# Turnout_Decoder_V1_1.net
KiCad netlist of a schematic drawn in EAGLE
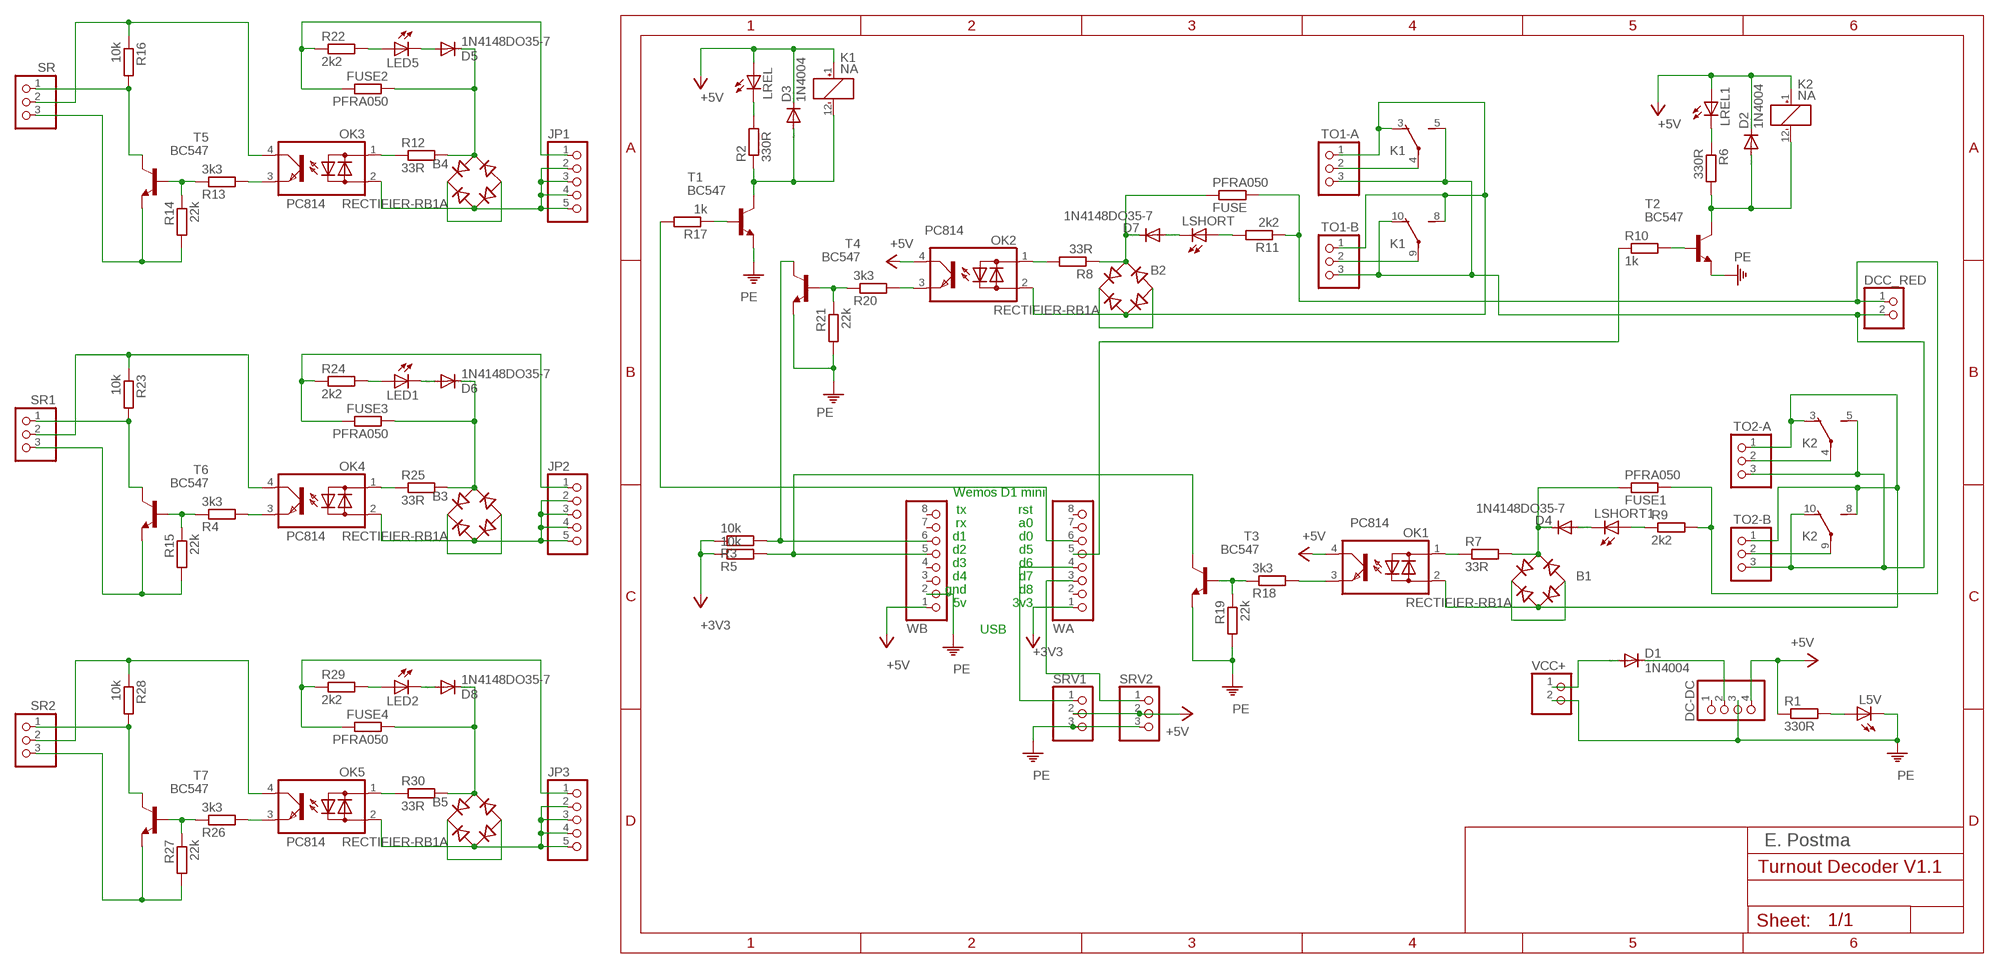
[diagram p0: schematic, sheet 1]

(export (version "E")
  (design (tool "Eeschema 10.0.6"))
  (components
    (comp (ref "B1")
      (value "RECTIFIER-RB1A")
      (footprint "eagle-import:RB1A")
      (libsource (lib "eagle-import") (part "RECTIFIER-RB1A"))
    )
    (comp (ref "B2")
      (value "RECTIFIER-RB1A")
      (footprint "eagle-import:RB1A")
      (libsource (lib "eagle-import") (part "RECTIFIER-RB1A"))
    )
    (comp (ref "B3")
      (value "RECTIFIER-RB1A")
      (footprint "eagle-import:RB1A")
      (libsource (lib "eagle-import") (part "RECTIFIER-RB1A"))
    )
    (comp (ref "B4")
      (value "RECTIFIER-RB1A")
      (footprint "eagle-import:RB1A")
      (libsource (lib "eagle-import") (part "RECTIFIER-RB1A"))
    )
    (comp (ref "B5")
      (value "RECTIFIER-RB1A")
      (footprint "eagle-import:RB1A")
      (libsource (lib "eagle-import") (part "RECTIFIER-RB1A"))
    )
    (comp (ref "D1")
      (value "1N4004")
      (footprint "eagle-import:DO41-10")
      (libsource (lib "eagle-import") (part "1N4004"))
    )
    (comp (ref "D2")
      (value "1N4004")
      (footprint "eagle-import:DO41-10")
      (libsource (lib "eagle-import") (part "1N4004"))
    )
    (comp (ref "D3")
      (value "1N4004")
      (footprint "eagle-import:DO41-10")
      (libsource (lib "eagle-import") (part "1N4004"))
    )
    (comp (ref "D4")
      (value "1N4148DO35-7")
      (footprint "eagle-import:DO35-7")
      (libsource (lib "eagle-import") (part "1N4148DO35-7"))
    )
    (comp (ref "D5")
      (value "1N4148DO35-7")
      (footprint "eagle-import:DO35-7")
      (libsource (lib "eagle-import") (part "1N4148DO35-7"))
    )
    (comp (ref "D6")
      (value "1N4148DO35-7")
      (footprint "eagle-import:DO35-7")
      (libsource (lib "eagle-import") (part "1N4148DO35-7"))
    )
    (comp (ref "D7")
      (value "1N4148DO35-7")
      (footprint "eagle-import:DO35-7")
      (libsource (lib "eagle-import") (part "1N4148DO35-7"))
    )
    (comp (ref "D8")
      (value "1N4148DO35-7")
      (footprint "eagle-import:DO35-7")
      (libsource (lib "eagle-import") (part "1N4148DO35-7"))
    )
    (comp (ref "DC-DC")
      (value "PINHD-1X4")
      (footprint "eagle-import:1X04")
      (libsource (lib "eagle-import") (part "PINHD-1X4"))
    )
    (comp (ref "DCC_RED")
      (value "PINHD-1X2")
      (footprint "eagle-import:1X02")
      (libsource (lib "eagle-import") (part "PINHD-1X2"))
    )
    (comp (ref "FUSE")
      (value "PFRA050")
      (footprint "eagle-import:0414V")
      (libsource (lib "eagle-import") (part "R-EU_0414/5V"))
    )
    (comp (ref "FUSE1")
      (value "PFRA050")
      (footprint "eagle-import:0414V")
      (libsource (lib "eagle-import") (part "R-EU_0414/5V"))
    )
    (comp (ref "FUSE2")
      (value "PFRA050")
      (footprint "eagle-import:0414V")
      (libsource (lib "eagle-import") (part "R-EU_0414/5V"))
    )
    (comp (ref "FUSE3")
      (value "PFRA050")
      (footprint "eagle-import:0414V")
      (libsource (lib "eagle-import") (part "R-EU_0414/5V"))
    )
    (comp (ref "FUSE4")
      (value "PFRA050")
      (footprint "eagle-import:0414V")
      (libsource (lib "eagle-import") (part "R-EU_0414/5V"))
    )
    (comp (ref "JP1")
      (value "PINHD-1X5")
      (footprint "eagle-import:1X05")
      (libsource (lib "eagle-import") (part "PINHD-1X5"))
    )
    (comp (ref "JP2")
      (value "PINHD-1X5")
      (footprint "eagle-import:1X05")
      (libsource (lib "eagle-import") (part "PINHD-1X5"))
    )
    (comp (ref "JP3")
      (value "PINHD-1X5")
      (footprint "eagle-import:1X05")
      (libsource (lib "eagle-import") (part "PINHD-1X5"))
    )
    (comp (ref "K1") (value "NA") (footprint "eagle-import:NA") (libsource (lib "eagle-import") (part "NA")))
    (comp (ref "K2") (value "NA") (footprint "eagle-import:NA") (libsource (lib "eagle-import") (part "NA")))
    (comp (ref "L5V")
      (value "LED3MM")
      (footprint "eagle-import:LED3MM")
      (libsource (lib "eagle-import") (part "LED3MM"))
    )
    (comp (ref "LED1")
      (value "LED3MM")
      (footprint "eagle-import:LED3MM")
      (libsource (lib "eagle-import") (part "LED3MM"))
    )
    (comp (ref "LED2")
      (value "LED3MM")
      (footprint "eagle-import:LED3MM")
      (libsource (lib "eagle-import") (part "LED3MM"))
    )
    (comp (ref "LED5")
      (value "LED3MM")
      (footprint "eagle-import:LED3MM")
      (libsource (lib "eagle-import") (part "LED3MM"))
    )
    (comp (ref "LREL")
      (value "LED3MM")
      (footprint "eagle-import:LED3MM")
      (libsource (lib "eagle-import") (part "LED3MM"))
    )
    (comp (ref "LREL1")
      (value "LED3MM")
      (footprint "eagle-import:LED3MM")
      (libsource (lib "eagle-import") (part "LED3MM"))
    )
    (comp (ref "LSHORT")
      (value "LED3MM")
      (footprint "eagle-import:LED3MM")
      (libsource (lib "eagle-import") (part "LED3MM"))
    )
    (comp (ref "LSHORT1")
      (value "LED3MM")
      (footprint "eagle-import:LED3MM")
      (libsource (lib "eagle-import") (part "LED3MM"))
    )
    (comp (ref "OK1")
      (value "PC814")
      (footprint "eagle-import:DIL04")
      (libsource (lib "eagle-import") (part "PC814"))
    )
    (comp (ref "OK2")
      (value "PC814")
      (footprint "eagle-import:DIL04")
      (libsource (lib "eagle-import") (part "PC814"))
    )
    (comp (ref "OK3")
      (value "PC814")
      (footprint "eagle-import:DIL04")
      (libsource (lib "eagle-import") (part "PC814"))
    )
    (comp (ref "OK4")
      (value "PC814")
      (footprint "eagle-import:DIL04")
      (libsource (lib "eagle-import") (part "PC814"))
    )
    (comp (ref "OK5")
      (value "PC814")
      (footprint "eagle-import:DIL04")
      (libsource (lib "eagle-import") (part "PC814"))
    )
    (comp (ref "R1")
      (value "330R")
      (footprint "eagle-import:0207_7")
      (libsource (lib "eagle-import") (part "resistor_348_R-EU_0207/7"))
    )
    (comp (ref "R2")
      (value "330R")
      (footprint "eagle-import:0207_7")
      (libsource (lib "eagle-import") (part "resistor_348_R-EU_0207/7"))
    )
    (comp (ref "R3")
      (value "10k")
      (footprint "eagle-import:0207_7")
      (libsource (lib "eagle-import") (part "resistor_348_R-EU_0207/7"))
    )
    (comp (ref "R4")
      (value "3k3")
      (footprint "eagle-import:0207_7")
      (libsource (lib "eagle-import") (part "resistor_348_R-EU_0207/7"))
    )
    (comp (ref "R5")
      (value "10k")
      (footprint "eagle-import:0207_7")
      (libsource (lib "eagle-import") (part "resistor_348_R-EU_0207/7"))
    )
    (comp (ref "R6")
      (value "330R")
      (footprint "eagle-import:0207_7")
      (libsource (lib "eagle-import") (part "resistor_348_R-EU_0207/7"))
    )
    (comp (ref "R7")
      (value "33R")
      (footprint "eagle-import:0207_7")
      (libsource (lib "eagle-import") (part "resistor_348_R-EU_0207/7"))
    )
    (comp (ref "R8")
      (value "33R")
      (footprint "eagle-import:0207_7")
      (libsource (lib "eagle-import") (part "resistor_348_R-EU_0207/7"))
    )
    (comp (ref "R9")
      (value "2k2")
      (footprint "eagle-import:0207_7")
      (libsource (lib "eagle-import") (part "resistor_348_R-EU_0207/7"))
    )
    (comp (ref "R10")
      (value "1k")
      (footprint "eagle-import:0207_7")
      (libsource (lib "eagle-import") (part "resistor_348_R-EU_0207/7"))
    )
    (comp (ref "R11")
      (value "2k2")
      (footprint "eagle-import:0207_7")
      (libsource (lib "eagle-import") (part "resistor_348_R-EU_0207/7"))
    )
    (comp (ref "R12")
      (value "33R")
      (footprint "eagle-import:0207_7")
      (libsource (lib "eagle-import") (part "resistor_348_R-EU_0207/7"))
    )
    (comp (ref "R13")
      (value "3k3")
      (footprint "eagle-import:0207_7")
      (libsource (lib "eagle-import") (part "resistor_348_R-EU_0207/7"))
    )
    (comp (ref "R14")
      (value "22k")
      (footprint "eagle-import:0207_7")
      (libsource (lib "eagle-import") (part "resistor_348_R-EU_0207/7"))
    )
    (comp (ref "R15")
      (value "22k")
      (footprint "eagle-import:0207_7")
      (libsource (lib "eagle-import") (part "resistor_348_R-EU_0207/7"))
    )
    (comp (ref "R16")
      (value "10k")
      (footprint "eagle-import:0207_7")
      (libsource (lib "eagle-import") (part "resistor_348_R-EU_0207/7"))
    )
    (comp (ref "R17")
      (value "1k")
      (footprint "eagle-import:0207_7")
      (libsource (lib "eagle-import") (part "resistor_348_R-EU_0207/7"))
    )
    (comp (ref "R18")
      (value "3k3")
      (footprint "eagle-import:0207_7")
      (libsource (lib "eagle-import") (part "resistor_348_R-EU_0207/7"))
    )
    (comp (ref "R19")
      (value "22k")
      (footprint "eagle-import:0207_7")
      (libsource (lib "eagle-import") (part "resistor_348_R-EU_0207/7"))
    )
    (comp (ref "R20")
      (value "3k3")
      (footprint "eagle-import:0207_7")
      (libsource (lib "eagle-import") (part "resistor_348_R-EU_0207/7"))
    )
    (comp (ref "R21")
      (value "22k")
      (footprint "eagle-import:0207_7")
      (libsource (lib "eagle-import") (part "resistor_348_R-EU_0207/7"))
    )
    (comp (ref "R22")
      (value "2k2")
      (footprint "eagle-import:0207_7")
      (libsource (lib "eagle-import") (part "resistor_348_R-EU_0207/7"))
    )
    (comp (ref "R23")
      (value "10k")
      (footprint "eagle-import:0207_7")
      (libsource (lib "eagle-import") (part "resistor_348_R-EU_0207/7"))
    )
    (comp (ref "R24")
      (value "2k2")
      (footprint "eagle-import:0207_7")
      (libsource (lib "eagle-import") (part "resistor_348_R-EU_0207/7"))
    )
    (comp (ref "R25")
      (value "33R")
      (footprint "eagle-import:0207_7")
      (libsource (lib "eagle-import") (part "resistor_348_R-EU_0207/7"))
    )
    (comp (ref "R26")
      (value "3k3")
      (footprint "eagle-import:0207_7")
      (libsource (lib "eagle-import") (part "resistor_348_R-EU_0207/7"))
    )
    (comp (ref "R27")
      (value "22k")
      (footprint "eagle-import:0207_7")
      (libsource (lib "eagle-import") (part "resistor_348_R-EU_0207/7"))
    )
    (comp (ref "R28")
      (value "10k")
      (footprint "eagle-import:0207_7")
      (libsource (lib "eagle-import") (part "resistor_348_R-EU_0207/7"))
    )
    (comp (ref "R29")
      (value "2k2")
      (footprint "eagle-import:0207_7")
      (libsource (lib "eagle-import") (part "resistor_348_R-EU_0207/7"))
    )
    (comp (ref "R30")
      (value "33R")
      (footprint "eagle-import:0207_7")
      (libsource (lib "eagle-import") (part "resistor_348_R-EU_0207/7"))
    )
    (comp (ref "SR")
      (value "PINHD-1X3")
      (footprint "eagle-import:1X03")
      (libsource (lib "eagle-import") (part "PINHD-1X3"))
    )
    (comp (ref "SR1")
      (value "PINHD-1X3")
      (footprint "eagle-import:1X03")
      (libsource (lib "eagle-import") (part "PINHD-1X3"))
    )
    (comp (ref "SR2")
      (value "PINHD-1X3")
      (footprint "eagle-import:1X03")
      (libsource (lib "eagle-import") (part "PINHD-1X3"))
    )
    (comp (ref "SRV1")
      (value "PINHD-1X3")
      (footprint "eagle-import:1X03")
      (libsource (lib "eagle-import") (part "PINHD-1X3"))
    )
    (comp (ref "SRV2")
      (value "PINHD-1X3")
      (footprint "eagle-import:1X03")
      (libsource (lib "eagle-import") (part "PINHD-1X3"))
    )
    (comp (ref "T1")
      (value "BC547")
      (footprint "eagle-import:TO92")
      (libsource (lib "eagle-import") (part "BC547"))
    )
    (comp (ref "T2")
      (value "BC547")
      (footprint "eagle-import:TO92")
      (libsource (lib "eagle-import") (part "BC547"))
    )
    (comp (ref "T3")
      (value "BC547")
      (footprint "eagle-import:TO92")
      (libsource (lib "eagle-import") (part "BC547"))
    )
    (comp (ref "T4")
      (value "BC547")
      (footprint "eagle-import:TO92")
      (libsource (lib "eagle-import") (part "BC547"))
    )
    (comp (ref "T5")
      (value "BC547")
      (footprint "eagle-import:TO92")
      (libsource (lib "eagle-import") (part "BC547"))
    )
    (comp (ref "T6")
      (value "BC547")
      (footprint "eagle-import:TO92")
      (libsource (lib "eagle-import") (part "BC547"))
    )
    (comp (ref "T7")
      (value "BC547")
      (footprint "eagle-import:TO92")
      (libsource (lib "eagle-import") (part "BC547"))
    )
    (comp (ref "TO1-A")
      (value "PINHD-1X3")
      (footprint "eagle-import:1X03")
      (libsource (lib "eagle-import") (part "PINHD-1X3"))
    )
    (comp (ref "TO1-B")
      (value "PINHD-1X3")
      (footprint "eagle-import:1X03")
      (libsource (lib "eagle-import") (part "PINHD-1X3"))
    )
    (comp (ref "TO2-A")
      (value "PINHD-1X3")
      (footprint "eagle-import:1X03")
      (libsource (lib "eagle-import") (part "PINHD-1X3"))
    )
    (comp (ref "TO2-B")
      (value "PINHD-1X3")
      (footprint "eagle-import:1X03")
      (libsource (lib "eagle-import") (part "PINHD-1X3"))
    )
    (comp (ref "VCC+")
      (value "PINHD-1X2")
      (footprint "eagle-import:1X02")
      (libsource (lib "eagle-import") (part "PINHD-1X2"))
    )
    (comp (ref "WA")
      (value "PINHD-1X8")
      (footprint "eagle-import:1X08")
      (libsource (lib "eagle-import") (part "PINHD-1X8"))
    )
    (comp (ref "WB")
      (value "PINHD-1X8")
      (footprint "eagle-import:1X08")
      (libsource (lib "eagle-import") (part "PINHD-1X8"))
    )
  )
  (nets
    (net (code "1") (name "+3V3") (class "Default")
      (node (ref "R3") (pin "1") (pinfunction "1_1") (pintype "passive"))
      (node (ref "R5") (pin "1") (pinfunction "1_1") (pintype "passive"))
      (node (ref "WA") (pin "1") (pinfunction "1_1") (pintype "passive"))
    )
    (net (code "2") (name "+5V") (class "Default")
      (node (ref "D2") (pin "C") (pinfunction "C_C") (pintype "passive"))
      (node (ref "D3") (pin "C") (pinfunction "C_C") (pintype "passive"))
      (node (ref "DC-DC") (pin "4") (pinfunction "4_4") (pintype "passive"))
      (node (ref "K1") (pin "1") (pinfunction "+_1") (pintype "passive"))
      (node (ref "K2") (pin "1") (pinfunction "+_1") (pintype "passive"))
      (node (ref "LREL") (pin "A") (pinfunction "A_A") (pintype "passive"))
      (node (ref "LREL1") (pin "A") (pinfunction "A_A") (pintype "passive"))
      (node (ref "OK1") (pin "4") (pinfunction "C_4") (pintype "passive"))
      (node (ref "OK2") (pin "4") (pinfunction "C_4") (pintype "passive"))
      (node (ref "R1") (pin "1") (pinfunction "1_1") (pintype "passive"))
      (node (ref "SRV1") (pin "2") (pinfunction "2_2") (pintype "passive"))
      (node (ref "SRV2") (pin "2") (pinfunction "2_2") (pintype "passive"))
      (node (ref "WB") (pin "1") (pinfunction "1_1") (pintype "passive"))
    )
    (net (code "3") (name "Net-(B1-Pad+)") (class "Default")
      (node (ref "B1") (pin "+") (pinfunction "+_+") (pintype "passive"))
      (node (ref "B1") (pin "-") (pinfunction "-_-") (pintype "passive"))
    )
    (net (code "4") (name "Net-(B1-PadAC1)") (class "Default")
      (node (ref "B1") (pin "AC1") (pinfunction "AC1_AC1") (pintype "passive"))
      (node (ref "D4") (pin "C") (pinfunction "C_C") (pintype "passive"))
      (node (ref "FUSE1") (pin "1") (pinfunction "1_1") (pintype "passive"))
      (node (ref "R7") (pin "2") (pinfunction "2_2") (pintype "passive"))
    )
    (net (code "5") (name "Net-(B2-Pad+)") (class "Default")
      (node (ref "B2") (pin "+") (pinfunction "+_+") (pintype "passive"))
      (node (ref "B2") (pin "-") (pinfunction "-_-") (pintype "passive"))
    )
    (net (code "6") (name "Net-(B2-PadAC1)") (class "Default")
      (node (ref "B2") (pin "AC1") (pinfunction "AC1_AC1") (pintype "passive"))
      (node (ref "D7") (pin "C") (pinfunction "C_C") (pintype "passive"))
      (node (ref "FUSE") (pin "1") (pinfunction "1_1") (pintype "passive"))
      (node (ref "R8") (pin "1") (pinfunction "1_1") (pintype "passive"))
    )
    (net (code "7") (name "Net-(B3-Pad+)") (class "Default")
      (node (ref "B3") (pin "+") (pinfunction "+_+") (pintype "passive"))
      (node (ref "B3") (pin "-") (pinfunction "-_-") (pintype "passive"))
    )
    (net (code "8") (name "Net-(B3-PadAC1)") (class "Default")
      (node (ref "B3") (pin "AC1") (pinfunction "AC1_AC1") (pintype "passive"))
      (node (ref "D6") (pin "C") (pinfunction "C_C") (pintype "passive"))
      (node (ref "FUSE3") (pin "1") (pinfunction "1_1") (pintype "passive"))
      (node (ref "R25") (pin "2") (pinfunction "2_2") (pintype "passive"))
    )
    (net (code "9") (name "Net-(B4-Pad+)") (class "Default")
      (node (ref "B4") (pin "+") (pinfunction "+_+") (pintype "passive"))
      (node (ref "B4") (pin "-") (pinfunction "-_-") (pintype "passive"))
    )
    (net (code "10") (name "Net-(B4-PadAC1)") (class "Default")
      (node (ref "B4") (pin "AC1") (pinfunction "AC1_AC1") (pintype "passive"))
      (node (ref "D5") (pin "C") (pinfunction "C_C") (pintype "passive"))
      (node (ref "FUSE2") (pin "1") (pinfunction "1_1") (pintype "passive"))
      (node (ref "R12") (pin "2") (pinfunction "2_2") (pintype "passive"))
    )
    (net (code "11") (name "Net-(B5-Pad+)") (class "Default")
      (node (ref "B5") (pin "+") (pinfunction "+_+") (pintype "passive"))
      (node (ref "B5") (pin "-") (pinfunction "-_-") (pintype "passive"))
    )
    (net (code "12") (name "Net-(B5-PadAC1)") (class "Default")
      (node (ref "B5") (pin "AC1") (pinfunction "AC1_AC1") (pintype "passive"))
      (node (ref "D8") (pin "C") (pinfunction "C_C") (pintype "passive"))
      (node (ref "FUSE4") (pin "1") (pinfunction "1_1") (pintype "passive"))
      (node (ref "R30") (pin "2") (pinfunction "2_2") (pintype "passive"))
    )
    (net (code "13") (name "Net-(D1-PadA)") (class "Default")
      (node (ref "D1") (pin "A") (pinfunction "A_A") (pintype "passive"))
      (node (ref "VCC+") (pin "1") (pinfunction "1_1") (pintype "passive"))
    )
    (net (code "14") (name "Net-(D1-PadC)") (class "Default")
      (node (ref "D1") (pin "C") (pinfunction "C_C") (pintype "passive"))
      (node (ref "DC-DC") (pin "2") (pinfunction "2_2") (pintype "passive"))
    )
    (net (code "15") (name "Net-(DCC_RED-Pad1)") (class "Default")
      (node (ref "DCC_RED") (pin "1") (pinfunction "1_1") (pintype "passive"))
      (node (ref "FUSE") (pin "2") (pinfunction "2_2") (pintype "passive"))
      (node (ref "FUSE1") (pin "2") (pinfunction "2_2") (pintype "passive"))
      (node (ref "R11") (pin "1") (pinfunction "1_1") (pintype "passive"))
      (node (ref "R9") (pin "2") (pinfunction "2_2") (pintype "passive"))
    )
    (net (code "16") (name "Net-(FUSE2-Pad2)") (class "Default")
      (node (ref "FUSE2") (pin "2") (pinfunction "2_2") (pintype "passive"))
      (node (ref "JP1") (pin "1") (pinfunction "1_1") (pintype "passive"))
      (node (ref "R22") (pin "1") (pinfunction "1_1") (pintype "passive"))
    )
    (net (code "17") (name "Net-(FUSE3-Pad2)") (class "Default")
      (node (ref "FUSE3") (pin "2") (pinfunction "2_2") (pintype "passive"))
      (node (ref "JP2") (pin "1") (pinfunction "1_1") (pintype "passive"))
      (node (ref "R24") (pin "1") (pinfunction "1_1") (pintype "passive"))
    )
    (net (code "18") (name "Net-(FUSE4-Pad2)") (class "Default")
      (node (ref "FUSE4") (pin "2") (pinfunction "2_2") (pintype "passive"))
      (node (ref "JP3") (pin "1") (pinfunction "1_1") (pintype "passive"))
      (node (ref "R29") (pin "1") (pinfunction "1_1") (pintype "passive"))
    )
    (net (code "19") (name "Net-(K1A--)") (class "Default")
      (node (ref "D3") (pin "A") (pinfunction "A_A") (pintype "passive"))
      (node (ref "K1") (pin "12") (pinfunction "-_12") (pintype "passive"))
      (node (ref "R2") (pin "1") (pinfunction "1_1") (pintype "passive"))
      (node (ref "T1") (pin "3") (pinfunction "C_3") (pintype "passive"))
    )
    (net (code "20") (name "Net-(K1B-O)") (class "Default")
      (node (ref "B2") (pin "AC2") (pinfunction "AC2_AC2") (pintype "passive"))
      (node (ref "K1") (pin "3") (pinfunction "O_3") (pintype "passive"))
      (node (ref "K1") (pin "8") (pinfunction "S_8") (pintype "passive"))
      (node (ref "OK2") (pin "2") (pinfunction "AC2_2") (pintype "passive"))
      (node (ref "TO1-A") (pin "1") (pinfunction "1_1") (pintype "passive"))
      (node (ref "TO1-B") (pin "1") (pinfunction "1_1") (pintype "passive"))
    )
    (net (code "21") (name "Net-(K1B-P)") (class "Default")
      (node (ref "K1") (pin "4") (pinfunction "P_4") (pintype "passive"))
      (node (ref "TO1-A") (pin "2") (pinfunction "2_2") (pintype "passive"))
    )
    (net (code "22") (name "Net-(K1B-S)") (class "Default")
      (node (ref "DCC_RED") (pin "2") (pinfunction "2_2") (pintype "passive"))
      (node (ref "K1") (pin "10") (pinfunction "O_10") (pintype "passive"))
      (node (ref "K1") (pin "5") (pinfunction "S_5") (pintype "passive"))
      (node (ref "K2") (pin "10") (pinfunction "O_10") (pintype "passive"))
      (node (ref "K2") (pin "5") (pinfunction "S_5") (pintype "passive"))
      (node (ref "TO1-A") (pin "3") (pinfunction "3_3") (pintype "passive"))
      (node (ref "TO1-B") (pin "3") (pinfunction "3_3") (pintype "passive"))
      (node (ref "TO2-A") (pin "3") (pinfunction "3_3") (pintype "passive"))
      (node (ref "TO2-B") (pin "3") (pinfunction "3_3") (pintype "passive"))
    )
    (net (code "23") (name "Net-(K1C-P)") (class "Default")
      (node (ref "K1") (pin "9") (pinfunction "P_9") (pintype "passive"))
      (node (ref "TO1-B") (pin "2") (pinfunction "2_2") (pintype "passive"))
    )
    (net (code "24") (name "Net-(K2A--)") (class "Default")
      (node (ref "D2") (pin "A") (pinfunction "A_A") (pintype "passive"))
      (node (ref "K2") (pin "12") (pinfunction "-_12") (pintype "passive"))
      (node (ref "R6") (pin "2") (pinfunction "2_2") (pintype "passive"))
      (node (ref "T2") (pin "3") (pinfunction "C_3") (pintype "passive"))
    )
    (net (code "25") (name "Net-(K2B-O)") (class "Default")
      (node (ref "B1") (pin "AC2") (pinfunction "AC2_AC2") (pintype "passive"))
      (node (ref "K2") (pin "3") (pinfunction "O_3") (pintype "passive"))
      (node (ref "K2") (pin "8") (pinfunction "S_8") (pintype "passive"))
      (node (ref "OK1") (pin "2") (pinfunction "AC2_2") (pintype "passive"))
      (node (ref "TO2-A") (pin "1") (pinfunction "1_1") (pintype "passive"))
      (node (ref "TO2-B") (pin "1") (pinfunction "1_1") (pintype "passive"))
    )
    (net (code "26") (name "Net-(K2B-P)") (class "Default")
      (node (ref "K2") (pin "4") (pinfunction "P_4") (pintype "passive"))
      (node (ref "TO2-A") (pin "2") (pinfunction "2_2") (pintype "passive"))
    )
    (net (code "27") (name "Net-(K2C-P)") (class "Default")
      (node (ref "K2") (pin "9") (pinfunction "P_9") (pintype "passive"))
      (node (ref "TO2-B") (pin "2") (pinfunction "2_2") (pintype "passive"))
    )
    (net (code "28") (name "Net-(L5V-PadA)") (class "Default")
      (node (ref "L5V") (pin "A") (pinfunction "A_A") (pintype "passive"))
      (node (ref "R1") (pin "2") (pinfunction "2_2") (pintype "passive"))
    )
    (net (code "29") (name "Net-(LED1-C)") (class "Default")
      (node (ref "D6") (pin "A") (pinfunction "A_A") (pintype "passive"))
      (node (ref "LED1") (pin "K") (pinfunction "C_K") (pintype "passive"))
    )
    (net (code "30") (name "Net-(LED1-PadA)") (class "Default")
      (node (ref "LED1") (pin "A") (pinfunction "A_A") (pintype "passive"))
      (node (ref "R24") (pin "2") (pinfunction "2_2") (pintype "passive"))
    )
    (net (code "31") (name "Net-(LED2-C)") (class "Default")
      (node (ref "D8") (pin "A") (pinfunction "A_A") (pintype "passive"))
      (node (ref "LED2") (pin "K") (pinfunction "C_K") (pintype "passive"))
    )
    (net (code "32") (name "Net-(LED2-PadA)") (class "Default")
      (node (ref "LED2") (pin "A") (pinfunction "A_A") (pintype "passive"))
      (node (ref "R29") (pin "2") (pinfunction "2_2") (pintype "passive"))
    )
    (net (code "33") (name "Net-(LED5-C)") (class "Default")
      (node (ref "D5") (pin "A") (pinfunction "A_A") (pintype "passive"))
      (node (ref "LED5") (pin "K") (pinfunction "C_K") (pintype "passive"))
    )
    (net (code "34") (name "Net-(LED5-PadA)") (class "Default")
      (node (ref "LED5") (pin "A") (pinfunction "A_A") (pintype "passive"))
      (node (ref "R22") (pin "2") (pinfunction "2_2") (pintype "passive"))
    )
    (net (code "35") (name "Net-(LREL-C)") (class "Default")
      (node (ref "LREL") (pin "K") (pinfunction "C_K") (pintype "passive"))
      (node (ref "R2") (pin "2") (pinfunction "2_2") (pintype "passive"))
    )
    (net (code "36") (name "Net-(LREL1-C)") (class "Default")
      (node (ref "LREL1") (pin "K") (pinfunction "C_K") (pintype "passive"))
      (node (ref "R6") (pin "1") (pinfunction "1_1") (pintype "passive"))
    )
    (net (code "37") (name "Net-(LSHORT-C)") (class "Default")
      (node (ref "D7") (pin "A") (pinfunction "A_A") (pintype "passive"))
      (node (ref "LSHORT") (pin "K") (pinfunction "C_K") (pintype "passive"))
    )
    (net (code "38") (name "Net-(LSHORT-PadA)") (class "Default")
      (node (ref "LSHORT") (pin "A") (pinfunction "A_A") (pintype "passive"))
      (node (ref "R11") (pin "2") (pinfunction "2_2") (pintype "passive"))
    )
    (net (code "39") (name "Net-(LSHORT1-C)") (class "Default")
      (node (ref "D4") (pin "A") (pinfunction "A_A") (pintype "passive"))
      (node (ref "LSHORT1") (pin "K") (pinfunction "C_K") (pintype "passive"))
    )
    (net (code "40") (name "Net-(LSHORT1-PadA)") (class "Default")
      (node (ref "LSHORT1") (pin "A") (pinfunction "A_A") (pintype "passive"))
      (node (ref "R9") (pin "1") (pinfunction "1_1") (pintype "passive"))
    )
    (net (code "41") (name "Net-(OK1-AC1)") (class "Default")
      (node (ref "OK1") (pin "1") (pinfunction "AC1_1") (pintype "passive"))
      (node (ref "R7") (pin "1") (pinfunction "1_1") (pintype "passive"))
    )
    (net (code "42") (name "Net-(OK1-E)") (class "Default")
      (node (ref "OK1") (pin "3") (pinfunction "E_3") (pintype "passive"))
      (node (ref "R18") (pin "2") (pinfunction "2_2") (pintype "passive"))
    )
    (net (code "43") (name "Net-(OK2-AC1)") (class "Default")
      (node (ref "OK2") (pin "1") (pinfunction "AC1_1") (pintype "passive"))
      (node (ref "R8") (pin "2") (pinfunction "2_2") (pintype "passive"))
    )
    (net (code "44") (name "Net-(OK2-E)") (class "Default")
      (node (ref "OK2") (pin "3") (pinfunction "E_3") (pintype "passive"))
      (node (ref "R20") (pin "2") (pinfunction "2_2") (pintype "passive"))
    )
    (net (code "45") (name "Net-(OK3-AC1)") (class "Default")
      (node (ref "OK3") (pin "1") (pinfunction "AC1_1") (pintype "passive"))
      (node (ref "R12") (pin "1") (pinfunction "1_1") (pintype "passive"))
    )
    (net (code "46") (name "Net-(OK3-AC2)") (class "Default")
      (node (ref "B4") (pin "AC2") (pinfunction "AC2_AC2") (pintype "passive"))
      (node (ref "JP1") (pin "2") (pinfunction "2_2") (pintype "passive"))
      (node (ref "JP1") (pin "3") (pinfunction "3_3") (pintype "passive"))
      (node (ref "JP1") (pin "4") (pinfunction "4_4") (pintype "passive"))
      (node (ref "JP1") (pin "5") (pinfunction "5_5") (pintype "passive"))
      (node (ref "OK3") (pin "2") (pinfunction "AC2_2") (pintype "passive"))
    )
    (net (code "47") (name "Net-(OK3-C)") (class "Default")
      (node (ref "OK3") (pin "4") (pinfunction "C_4") (pintype "passive"))
      (node (ref "R16") (pin "1") (pinfunction "1_1") (pintype "passive"))
      (node (ref "SR") (pin "2") (pinfunction "2_2") (pintype "passive"))
    )
    (net (code "48") (name "Net-(OK3-E)") (class "Default")
      (node (ref "OK3") (pin "3") (pinfunction "E_3") (pintype "passive"))
      (node (ref "R13") (pin "2") (pinfunction "2_2") (pintype "passive"))
    )
    (net (code "49") (name "Net-(OK4-AC1)") (class "Default")
      (node (ref "OK4") (pin "1") (pinfunction "AC1_1") (pintype "passive"))
      (node (ref "R25") (pin "1") (pinfunction "1_1") (pintype "passive"))
    )
    (net (code "50") (name "Net-(OK4-AC2)") (class "Default")
      (node (ref "B3") (pin "AC2") (pinfunction "AC2_AC2") (pintype "passive"))
      (node (ref "JP2") (pin "2") (pinfunction "2_2") (pintype "passive"))
      (node (ref "JP2") (pin "3") (pinfunction "3_3") (pintype "passive"))
      (node (ref "JP2") (pin "4") (pinfunction "4_4") (pintype "passive"))
      (node (ref "JP2") (pin "5") (pinfunction "5_5") (pintype "passive"))
      (node (ref "OK4") (pin "2") (pinfunction "AC2_2") (pintype "passive"))
    )
    (net (code "51") (name "Net-(OK4-C)") (class "Default")
      (node (ref "OK4") (pin "4") (pinfunction "C_4") (pintype "passive"))
      (node (ref "R23") (pin "1") (pinfunction "1_1") (pintype "passive"))
      (node (ref "SR1") (pin "2") (pinfunction "2_2") (pintype "passive"))
    )
    (net (code "52") (name "Net-(OK4-E)") (class "Default")
      (node (ref "OK4") (pin "3") (pinfunction "E_3") (pintype "passive"))
      (node (ref "R4") (pin "2") (pinfunction "2_2") (pintype "passive"))
    )
    (net (code "53") (name "Net-(OK5-AC1)") (class "Default")
      (node (ref "OK5") (pin "1") (pinfunction "AC1_1") (pintype "passive"))
      (node (ref "R30") (pin "1") (pinfunction "1_1") (pintype "passive"))
    )
    (net (code "54") (name "Net-(OK5-AC2)") (class "Default")
      (node (ref "B5") (pin "AC2") (pinfunction "AC2_AC2") (pintype "passive"))
      (node (ref "JP3") (pin "2") (pinfunction "2_2") (pintype "passive"))
      (node (ref "JP3") (pin "3") (pinfunction "3_3") (pintype "passive"))
      (node (ref "JP3") (pin "4") (pinfunction "4_4") (pintype "passive"))
      (node (ref "JP3") (pin "5") (pinfunction "5_5") (pintype "passive"))
      (node (ref "OK5") (pin "2") (pinfunction "AC2_2") (pintype "passive"))
    )
    (net (code "55") (name "Net-(OK5-C)") (class "Default")
      (node (ref "OK5") (pin "4") (pinfunction "C_4") (pintype "passive"))
      (node (ref "R28") (pin "1") (pinfunction "1_1") (pintype "passive"))
      (node (ref "SR2") (pin "2") (pinfunction "2_2") (pintype "passive"))
    )
    (net (code "56") (name "Net-(OK5-E)") (class "Default")
      (node (ref "OK5") (pin "3") (pinfunction "E_3") (pintype "passive"))
      (node (ref "R26") (pin "2") (pinfunction "2_2") (pintype "passive"))
    )
    (net (code "57") (name "Net-(R10-Pad1)") (class "Default")
      (node (ref "R10") (pin "1") (pinfunction "1_1") (pintype "passive"))
      (node (ref "WA") (pin "5") (pinfunction "5_5") (pintype "passive"))
    )
    (net (code "58") (name "Net-(R17-Pad2)") (class "Default")
      (node (ref "R17") (pin "2") (pinfunction "2_2") (pintype "passive"))
      (node (ref "WA") (pin "6") (pinfunction "6_6") (pintype "passive"))
    )
    (net (code "59") (name "Net-(SRV1-Pad1)") (class "Default")
      (node (ref "SRV1") (pin "1") (pinfunction "1_1") (pintype "passive"))
      (node (ref "WA") (pin "4") (pinfunction "4_4") (pintype "passive"))
    )
    (net (code "60") (name "Net-(SRV2-Pad1)") (class "Default")
      (node (ref "SRV2") (pin "1") (pinfunction "1_1") (pintype "passive"))
      (node (ref "WA") (pin "3") (pinfunction "3_3") (pintype "passive"))
    )
    (net (code "61") (name "Net-(T1-B)") (class "Default")
      (node (ref "R17") (pin "1") (pinfunction "1_1") (pintype "passive"))
      (node (ref "T1") (pin "2") (pinfunction "B_2") (pintype "passive"))
    )
    (net (code "62") (name "Net-(T2-B)") (class "Default")
      (node (ref "R10") (pin "2") (pinfunction "2_2") (pintype "passive"))
      (node (ref "T2") (pin "2") (pinfunction "B_2") (pintype "passive"))
    )
    (net (code "63") (name "Net-(T3-B)") (class "Default")
      (node (ref "R18") (pin "1") (pinfunction "1_1") (pintype "passive"))
      (node (ref "R19") (pin "1") (pinfunction "1_1") (pintype "passive"))
      (node (ref "T3") (pin "2") (pinfunction "B_2") (pintype "passive"))
    )
    (net (code "64") (name "Net-(T3-C)") (class "Default")
      (node (ref "R5") (pin "2") (pinfunction "2_2") (pintype "passive"))
      (node (ref "T3") (pin "3") (pinfunction "C_3") (pintype "passive"))
      (node (ref "WB") (pin "5") (pinfunction "5_5") (pintype "passive"))
    )
    (net (code "65") (name "Net-(T4-B)") (class "Default")
      (node (ref "R20") (pin "1") (pinfunction "1_1") (pintype "passive"))
      (node (ref "R21") (pin "1") (pinfunction "1_1") (pintype "passive"))
      (node (ref "T4") (pin "2") (pinfunction "B_2") (pintype "passive"))
    )
    (net (code "66") (name "Net-(T4-C)") (class "Default")
      (node (ref "R3") (pin "2") (pinfunction "2_2") (pintype "passive"))
      (node (ref "T4") (pin "3") (pinfunction "C_3") (pintype "passive"))
      (node (ref "WB") (pin "6") (pinfunction "6_6") (pintype "passive"))
    )
    (net (code "67") (name "Net-(T5-B)") (class "Default")
      (node (ref "R13") (pin "1") (pinfunction "1_1") (pintype "passive"))
      (node (ref "R14") (pin "1") (pinfunction "1_1") (pintype "passive"))
      (node (ref "T5") (pin "2") (pinfunction "B_2") (pintype "passive"))
    )
    (net (code "68") (name "Net-(T5-C)") (class "Default")
      (node (ref "R16") (pin "2") (pinfunction "2_2") (pintype "passive"))
      (node (ref "SR") (pin "1") (pinfunction "1_1") (pintype "passive"))
      (node (ref "T5") (pin "3") (pinfunction "C_3") (pintype "passive"))
    )
    (net (code "69") (name "Net-(T5-E)") (class "Default")
      (node (ref "R14") (pin "2") (pinfunction "2_2") (pintype "passive"))
      (node (ref "SR") (pin "3") (pinfunction "3_3") (pintype "passive"))
      (node (ref "T5") (pin "1") (pinfunction "E_1") (pintype "passive"))
    )
    (net (code "70") (name "Net-(T6-B)") (class "Default")
      (node (ref "R15") (pin "1") (pinfunction "1_1") (pintype "passive"))
      (node (ref "R4") (pin "1") (pinfunction "1_1") (pintype "passive"))
      (node (ref "T6") (pin "2") (pinfunction "B_2") (pintype "passive"))
    )
    (net (code "71") (name "Net-(T6-C)") (class "Default")
      (node (ref "R23") (pin "2") (pinfunction "2_2") (pintype "passive"))
      (node (ref "SR1") (pin "1") (pinfunction "1_1") (pintype "passive"))
      (node (ref "T6") (pin "3") (pinfunction "C_3") (pintype "passive"))
    )
    (net (code "72") (name "Net-(T6-E)") (class "Default")
      (node (ref "R15") (pin "2") (pinfunction "2_2") (pintype "passive"))
      (node (ref "SR1") (pin "3") (pinfunction "3_3") (pintype "passive"))
      (node (ref "T6") (pin "1") (pinfunction "E_1") (pintype "passive"))
    )
    (net (code "73") (name "Net-(T7-B)") (class "Default")
      (node (ref "R26") (pin "1") (pinfunction "1_1") (pintype "passive"))
      (node (ref "R27") (pin "1") (pinfunction "1_1") (pintype "passive"))
      (node (ref "T7") (pin "2") (pinfunction "B_2") (pintype "passive"))
    )
    (net (code "74") (name "Net-(T7-C)") (class "Default")
      (node (ref "R28") (pin "2") (pinfunction "2_2") (pintype "passive"))
      (node (ref "SR2") (pin "1") (pinfunction "1_1") (pintype "passive"))
      (node (ref "T7") (pin "3") (pinfunction "C_3") (pintype "passive"))
    )
    (net (code "75") (name "Net-(T7-E)") (class "Default")
      (node (ref "R27") (pin "2") (pinfunction "2_2") (pintype "passive"))
      (node (ref "SR2") (pin "3") (pinfunction "3_3") (pintype "passive"))
      (node (ref "T7") (pin "1") (pinfunction "E_1") (pintype "passive"))
    )
    (net (code "76") (name "PE") (class "Default")
      (node (ref "DC-DC") (pin "3") (pinfunction "3_3") (pintype "passive"))
      (node (ref "L5V") (pin "K") (pinfunction "C_K") (pintype "passive"))
      (node (ref "R19") (pin "2") (pinfunction "2_2") (pintype "passive"))
      (node (ref "R21") (pin "2") (pinfunction "2_2") (pintype "passive"))
      (node (ref "SRV1") (pin "3") (pinfunction "3_3") (pintype "passive"))
      (node (ref "SRV2") (pin "3") (pinfunction "3_3") (pintype "passive"))
      (node (ref "T1") (pin "1") (pinfunction "E_1") (pintype "passive"))
      (node (ref "T2") (pin "1") (pinfunction "E_1") (pintype "passive"))
      (node (ref "T3") (pin "1") (pinfunction "E_1") (pintype "passive"))
      (node (ref "T4") (pin "1") (pinfunction "E_1") (pintype "passive"))
      (node (ref "VCC+") (pin "2") (pinfunction "2_2") (pintype "passive"))
      (node (ref "WB") (pin "2") (pinfunction "2_2") (pintype "passive"))
    )
    (net (code "77") (name "unconnected-(DC-DC-Pad1)") (class "Default")
      (node (ref "DC-DC") (pin "1") (pinfunction "1_1") (pintype "passive"))
    )
    (net (code "78") (name "unconnected-(WA-Pad2)") (class "Default")
      (node (ref "WA") (pin "2") (pinfunction "2_2") (pintype "passive"))
    )
    (net (code "79") (name "unconnected-(WA-Pad7)") (class "Default")
      (node (ref "WA") (pin "7") (pinfunction "7_7") (pintype "passive"))
    )
    (net (code "80") (name "unconnected-(WA-Pad8)") (class "Default")
      (node (ref "WA") (pin "8") (pinfunction "8_8") (pintype "passive"))
    )
    (net (code "81") (name "unconnected-(WB-Pad3)") (class "Default")
      (node (ref "WB") (pin "3") (pinfunction "3_3") (pintype "passive"))
    )
    (net (code "82") (name "unconnected-(WB-Pad4)") (class "Default")
      (node (ref "WB") (pin "4") (pinfunction "4_4") (pintype "passive"))
    )
    (net (code "83") (name "unconnected-(WB-Pad7)") (class "Default")
      (node (ref "WB") (pin "7") (pinfunction "7_7") (pintype "passive"))
    )
    (net (code "84") (name "unconnected-(WB-Pad8)") (class "Default")
      (node (ref "WB") (pin "8") (pinfunction "8_8") (pintype "passive"))
    )
  )
)
